# SW6106_A_B_C_Lighting_LED.net
KiCad netlist of a schematic drawn in Altium Designer
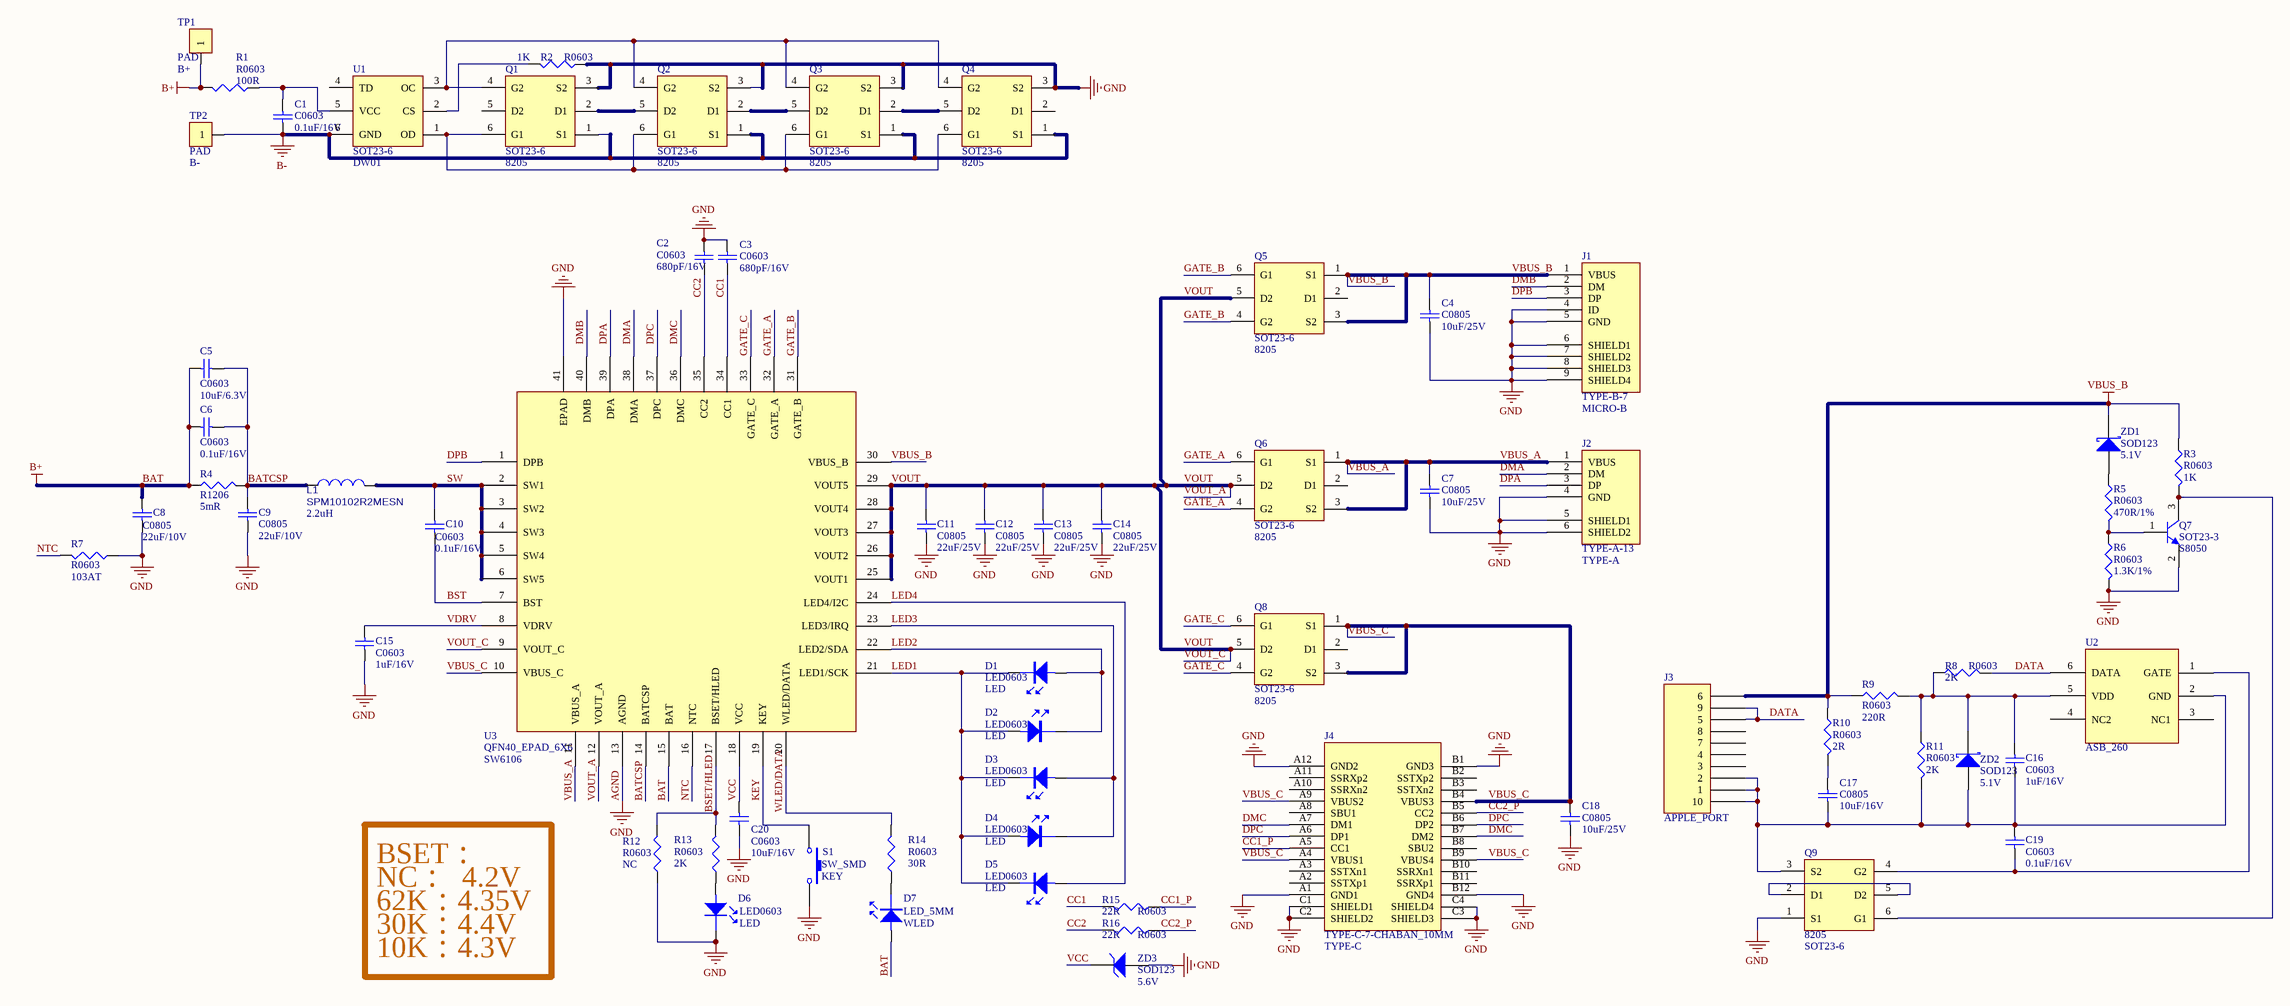
[diagram p0: SW6106+A+B+C+Lighting+LED.SchDoc]

(export (version "E")
  (design (tool "Eeschema 10.0.6"))
  (components
    (comp (ref "C1")
      (value "C0603")
      (footprint "C0603")
      (description "Capacitor")
      (fields (field (name "ALTIUM_VALUE") "0.1uF/16V") (field (name "PUBLISHER") "Altium Limited"))
      (libsource (lib "*") (part "Cap"))
    )
    (comp (ref "C2")
      (value "C0603")
      (footprint "C0603")
      (description "Capacitor")
      (fields (field (name "ALTIUM_VALUE") "680pF/16V") (field (name "PUBLISHER") "Altium Limited"))
      (libsource (lib "*") (part "CAP0603"))
    )
    (comp (ref "C3")
      (value "C0603")
      (footprint "C0603")
      (description "Capacitor")
      (fields (field (name "ALTIUM_VALUE") "680pF/16V") (field (name "PUBLISHER") "Altium Limited"))
      (libsource (lib "*") (part "CAP0603"))
    )
    (comp (ref "C4")
      (value "C0805")
      (footprint "C0805")
      (description "Capacitor")
      (fields (field (name "ALTIUM_VALUE") "10uF/25V") (field (name "PUBLISHER") "Altium Limited"))
      (libsource (lib "*") (part "CAP0603"))
    )
    (comp (ref "C5")
      (value "C0603")
      (footprint "C0603")
      (description "Capacitor")
      (fields (field (name "ALTIUM_VALUE") "10uF/6.3V") (field (name "PUBLISHER") "Altium Limited"))
      (libsource (lib "*") (part "CAP0603"))
    )
    (comp (ref "C6")
      (value "C0603")
      (footprint "C0603")
      (description "Capacitor")
      (fields (field (name "ALTIUM_VALUE") "0.1uF/16V") (field (name "PUBLISHER") "Altium Limited"))
      (libsource (lib "*") (part "CAP0603"))
    )
    (comp (ref "C7")
      (value "C0805")
      (footprint "C0805")
      (description "Capacitor")
      (fields (field (name "ALTIUM_VALUE") "10uF/25V") (field (name "PUBLISHER") "Altium Limited"))
      (libsource (lib "*") (part "CAP0603"))
    )
    (comp (ref "C8")
      (value "C0805")
      (footprint "C0805")
      (description "Capacitor")
      (fields (field (name "ALTIUM_VALUE") "22uF/10V") (field (name "PUBLISHER") "Altium Limited"))
      (libsource (lib "*") (part "CAP0805"))
    )
    (comp (ref "C9")
      (value "C0805")
      (footprint "C0805")
      (description "Capacitor")
      (fields (field (name "ALTIUM_VALUE") "22uF/10V") (field (name "PUBLISHER") "Altium Limited"))
      (libsource (lib "*") (part "CAP0805"))
    )
    (comp (ref "C10")
      (value "C0603")
      (footprint "C0603")
      (description "Capacitor")
      (fields (field (name "ALTIUM_VALUE") "0.1uF/16V") (field (name "PUBLISHER") "Altium Limited"))
      (libsource (lib "*") (part "CAP0603"))
    )
    (comp (ref "C11")
      (value "C0805")
      (footprint "C0805")
      (description "Capacitor")
      (fields (field (name "ALTIUM_VALUE") "22uF/25V") (field (name "PUBLISHER") "Altium Limited"))
      (libsource (lib "*") (part "CAP0805"))
    )
    (comp (ref "C12")
      (value "C0805")
      (footprint "C0805")
      (description "Capacitor")
      (fields (field (name "ALTIUM_VALUE") "22uF/25V") (field (name "PUBLISHER") "Altium Limited"))
      (libsource (lib "*") (part "CAP0805"))
    )
    (comp (ref "C13")
      (value "C0805")
      (footprint "C0805")
      (description "Capacitor")
      (fields (field (name "ALTIUM_VALUE") "22uF/25V") (field (name "PUBLISHER") "Altium Limited"))
      (libsource (lib "*") (part "CAP0805"))
    )
    (comp (ref "C14")
      (value "C0805")
      (footprint "C0805")
      (description "Capacitor")
      (fields (field (name "ALTIUM_VALUE") "22uF/25V") (field (name "PUBLISHER") "Altium Limited"))
      (libsource (lib "*") (part "CAP0805"))
    )
    (comp (ref "C15")
      (value "C0603")
      (footprint "C0603")
      (description "Capacitor")
      (fields (field (name "ALTIUM_VALUE") "1uF/16V") (field (name "PUBLISHER") "Altium Limited"))
      (libsource (lib "*") (part "CAP0603"))
    )
    (comp (ref "C16")
      (value "C0603")
      (footprint "C0603")
      (description "Capacitor")
      (fields (field (name "ALTIUM_VALUE") "1uF/16V") (field (name "PUBLISHER") "Altium Limited"))
      (libsource (lib "*") (part "CAP0805"))
    )
    (comp (ref "C17")
      (value "C0805")
      (footprint "C0805")
      (description "Capacitor")
      (fields (field (name "ALTIUM_VALUE") "10uF/16V") (field (name "PUBLISHER") "Altium Limited"))
      (libsource (lib "*") (part "CAP0805"))
    )
    (comp (ref "C18")
      (value "C0805")
      (footprint "C0805")
      (description "Capacitor")
      (fields (field (name "ALTIUM_VALUE") "10uF/25V") (field (name "PUBLISHER") "Altium Limited"))
      (libsource (lib "*") (part "CAP0603"))
    )
    (comp (ref "C19")
      (value "C0603")
      (footprint "C0603")
      (description "Capacitor")
      (fields (field (name "ALTIUM_VALUE") "0.1uF/16V") (field (name "PUBLISHER") "Altium Limited"))
      (libsource (lib "*") (part "CAP0805"))
    )
    (comp (ref "C20")
      (value "C0603")
      (footprint "C0603")
      (description "Capacitor")
      (fields (field (name "ALTIUM_VALUE") "10uF/16V") (field (name "PUBLISHER") "Altium Limited"))
      (libsource (lib "*") (part "CAP0603"))
    )
    (comp (ref "D1") (value "LED") (footprint "LED0603") (libsource (lib "*") (part "LED")))
    (comp (ref "D2") (value "LED") (footprint "LED0603") (libsource (lib "*") (part "LED")))
    (comp (ref "D3") (value "LED") (footprint "LED0603") (libsource (lib "*") (part "LED")))
    (comp (ref "D4") (value "LED") (footprint "LED0603") (libsource (lib "*") (part "LED")))
    (comp (ref "D5") (value "LED") (footprint "LED0603") (libsource (lib "*") (part "LED")))
    (comp (ref "D6") (value "LED") (footprint "LED0603") (libsource (lib "*") (part "LED")))
    (comp (ref "D7")
      (value "WLED")
      (footprint "LED_5MM")
      (fields (field (name "FOOTPRINF") "LED_5MM") (field (name "Comment") "LED_5MM"))
      (libsource (lib "*") (part "LED"))
    )
    (comp (ref "J1")
      (value "MICRO-B")
      (footprint "TYPE-B-7")
      (fields (field (name "FOOTPRINTF") "TYPE-B-7") (field (name "Comment") "USB_MICRO_B"))
      (libsource (lib "*") (part "USB_MICRO_B"))
    )
    (comp (ref "J2")
      (value "TYPE-A")
      (footprint "TYPE-A-13")
      (fields (field (name "FOOTPRINF") "TYPE-A-13") (field (name "Comment") "TYPE-A-1"))
      (libsource (lib "*") (part "TYPE-A-1"))
    )
    (comp (ref "J3") (value "APPLE_PORT") (libsource (lib "TEST") (part "APPLE_PORT")))
    (comp (ref "J4")
      (value "TYPE-C")
      (footprint "TYPE-C-7-CHABAN_10MM")
      (libsource (lib "*") (part "TYPE-C"))
    )
    (comp (ref "L1")
      (value "SPM10102R2MESN")
      (footprint "INDUCTOR_SPM1010")
      (fields (field (name "ALTIUM_VALUE") "2.2uH"))
      (libsource (lib "*") (part "INDUCTOR"))
    )
    (comp (ref "Q1")
      (value "8205")
      (footprint "SOT23-6")
      (fields (field (name "FOOTPRINF") "SOT23-6"))
      (libsource (lib "") (part "8205B_1"))
    )
    (comp (ref "Q2")
      (value "8205")
      (footprint "SOT23-6")
      (fields (field (name "FOOTPRINF") "SOT23-6"))
      (libsource (lib "") (part "8205B_1"))
    )
    (comp (ref "Q3")
      (value "8205")
      (footprint "SOT23-6")
      (fields (field (name "FOOTPRINF") "SOT23-6"))
      (libsource (lib "") (part "8205B_1"))
    )
    (comp (ref "Q4")
      (value "8205")
      (footprint "SOT23-6")
      (fields (field (name "FOOTPRINF") "SOT23-6"))
      (libsource (lib "") (part "8205B_1"))
    )
    (comp (ref "Q5")
      (value "8205")
      (footprint "SOT23-6")
      (fields (field (name "FOOTPRINF") "SOT23-6"))
      (libsource (lib "*") (part "8205B"))
    )
    (comp (ref "Q6")
      (value "8205")
      (footprint "SOT23-6")
      (fields (field (name "FOOTPRINF") "SOT23-6"))
      (libsource (lib "*") (part "8205B"))
    )
    (comp (ref "Q7")
      (value "S8050")
      (footprint "SOT23-3")
      (description "NPN General Purpose Amplifier")
      (fields (field (name "PUBLISHER") "Altium Limited"))
      (libsource (lib "Miscellaneous Devices") (part "2N3904"))
    )
    (comp (ref "Q8")
      (value "8205")
      (footprint "SOT23-6")
      (fields (field (name "FOOTPRINF") "SOT23-6"))
      (libsource (lib "*") (part "8205B"))
    )
    (comp (ref "Q9")
      (value "8205")
      (footprint "SOT23-6")
      (fields (field (name "FOOTPRINF") "SOT23-6"))
      (libsource (lib "") (part "8205B_2"))
    )
    (comp (ref "R1")
      (value "R0603")
      (footprint "R0603")
      (description "Resistor")
      (fields (field (name "ALTIUM_VALUE") "100R") (field (name "PUBLISHER") "Altium Limited"))
      (libsource (lib "*") (part "Res3"))
    )
    (comp (ref "R2")
      (value "R0603")
      (footprint "R0603")
      (description "Resistor")
      (fields (field (name "ALTIUM_VALUE") "1K") (field (name "PUBLISHER") "Altium Limited"))
      (libsource (lib "*") (part "Res3"))
    )
    (comp (ref "R3")
      (value "R0603")
      (footprint "R0603")
      (description "Resistor")
      (fields (field (name "ALTIUM_VALUE") "1K") (field (name "PUBLISHER") "Altium Limited"))
      (libsource (lib "Miscellaneous Devices") (part "Res3"))
    )
    (comp (ref "R4")
      (value "R1206")
      (footprint "R1206")
      (description "Resistor")
      (fields (field (name "ALTIUM_VALUE") "5mR") (field (name "PUBLISHER") "Altium Limited"))
      (libsource (lib "*") (part "RES"))
    )
    (comp (ref "R5")
      (value "R0603")
      (footprint "R0603")
      (description "Resistor")
      (fields (field (name "ALTIUM_VALUE") "470R/1%") (field (name "PUBLISHER") "Altium Limited"))
      (libsource (lib "Miscellaneous Devices") (part "Res3"))
    )
    (comp (ref "R6")
      (value "R0603")
      (footprint "R0603")
      (description "Resistor")
      (fields (field (name "ALTIUM_VALUE") "1.3K/1%") (field (name "PUBLISHER") "Altium Limited"))
      (libsource (lib "Miscellaneous Devices") (part "Res3"))
    )
    (comp (ref "R7")
      (value "R0603")
      (footprint "R0603")
      (description "Resistor")
      (fields (field (name "ALTIUM_VALUE") "103AT") (field (name "PUBLISHER") "Altium Limited"))
      (libsource (lib "*") (part "RES"))
    )
    (comp (ref "R8")
      (value "R0603")
      (footprint "R0603")
      (description "Resistor")
      (fields (field (name "ALTIUM_VALUE") "2K") (field (name "PUBLISHER") "Altium Limited"))
      (libsource (lib "Miscellaneous Devices") (part "Res3"))
    )
    (comp (ref "R9")
      (value "R0603")
      (footprint "R0603")
      (description "Resistor")
      (fields (field (name "ALTIUM_VALUE") "220R") (field (name "PUBLISHER") "Altium Limited"))
      (libsource (lib "Miscellaneous Devices") (part "Res3"))
    )
    (comp (ref "R10")
      (value "R0603")
      (footprint "R0603")
      (description "Resistor")
      (fields (field (name "ALTIUM_VALUE") "2R") (field (name "PUBLISHER") "Altium Limited"))
      (libsource (lib "Miscellaneous Devices") (part "Res3"))
    )
    (comp (ref "R11")
      (value "R0603")
      (footprint "R0603")
      (description "Resistor")
      (fields (field (name "ALTIUM_VALUE") "2K") (field (name "PUBLISHER") "Altium Limited"))
      (libsource (lib "Miscellaneous Devices") (part "Res3"))
    )
    (comp (ref "R12")
      (value "R0603")
      (footprint "R0603")
      (description "Resistor")
      (fields (field (name "ALTIUM_VALUE") "NC") (field (name "PUBLISHER") "Altium Limited"))
      (libsource (lib "*") (part "RES"))
    )
    (comp (ref "R13")
      (value "R0603")
      (footprint "R0603")
      (description "Resistor")
      (fields (field (name "ALTIUM_VALUE") "2K") (field (name "PUBLISHER") "Altium Limited"))
      (libsource (lib "*") (part "RES"))
    )
    (comp (ref "R14")
      (value "R0603")
      (footprint "R0603")
      (description "Resistor")
      (fields (field (name "ALTIUM_VALUE") "30R") (field (name "PUBLISHER") "Altium Limited"))
      (libsource (lib "*") (part "RES"))
    )
    (comp (ref "R15")
      (value "R0603")
      (footprint "R0603")
      (description "Resistor")
      (fields (field (name "ALTIUM_VALUE") "22R") (field (name "PUBLISHER") "Altium Limited"))
      (libsource (lib "*") (part "RES"))
    )
    (comp (ref "R16")
      (value "R0603")
      (footprint "R0603")
      (description "Resistor")
      (fields (field (name "ALTIUM_VALUE") "22R") (field (name "PUBLISHER") "Altium Limited"))
      (libsource (lib "*") (part "RES"))
    )
    (comp (ref "S1")
      (value "KEY")
      (footprint "SW_SMD")
      (fields (field (name "FOOTPRINF") "SW_SMD"))
      (libsource (lib "*") (part "SW K"))
    )
    (comp (ref "TP1") (value "B+") (footprint "PAD") (libsource (lib "") (part "Test Point_1")))
    (comp (ref "TP2") (value "B-") (footprint "PAD") (libsource (lib "*") (part "Test Point")))
    (comp (ref "U1")
      (value "DW01")
      (footprint "SOT23-6")
      (fields (field (name "FOOTPRINF") "SOT23-6"))
      (libsource (lib "*") (part "DW01"))
    )
    (comp (ref "U2") (value "ASB_260") (footprint "SOT-23-") (libsource (lib "TEST") (part "ASB_260")))
    (comp (ref "U3")
      (value "SW6106")
      (footprint "QFN40_EPAD_6X6")
      (libsource (lib "TEST") (part "SW6106_AFC"))
    )
    (comp (ref "ZD1")
      (value "5.1V")
      (footprint "SOD123")
      (description "Schottky Rectifier")
      (fields (field (name "Comment") "Diode 11DQ03") (field (name "PUBLISHER") "Altium Limited"))
      (libsource (lib "Miscellaneous Devices") (part "Diode 11DQ03"))
    )
    (comp (ref "ZD2")
      (value "5.1V")
      (footprint "SOD123")
      (description "Schottky Rectifier")
      (fields (field (name "Comment") "Diode 11DQ03") (field (name "PUBLISHER") "Altium Limited"))
      (libsource (lib "Miscellaneous Devices") (part "Diode 11DQ03"))
    )
    (comp (ref "ZD3")
      (value "SOD123")
      (footprint "SOD-123")
      (description "Zener Diode")
      (fields (field (name "ALTIUM_UNNAMED_1") "5.6V"))
      (libsource (lib "Miscellaneous Devices") (part "D Zener"))
    )
  )
  (nets
    (net (code "1") (name "/BATCSP") (class "Default")
      (node (ref "C5") (pin "2") (pinfunction "2_2") (pintype "passive"))
      (node (ref "C6") (pin "2") (pinfunction "2_2") (pintype "passive"))
      (node (ref "C9") (pin "2") (pinfunction "2_2") (pintype "passive"))
      (node (ref "L1") (pin "1") (pinfunction "1_1") (pintype "passive"))
      (node (ref "R4") (pin "2") (pinfunction "2_2") (pintype "passive"))
      (node (ref "U3") (pin "14") (pinfunction "BATCSP_14") (pintype "passive"))
    )
    (net (code "2") (name "/BSET{slash}HLED") (class "Default")
      (node (ref "R12") (pin "2") (pinfunction "2_2") (pintype "passive"))
      (node (ref "R13") (pin "2") (pinfunction "2_2") (pintype "passive"))
      (node (ref "U3") (pin "17") (pinfunction "BSET/HLED_17") (pintype "passive"))
    )
    (net (code "3") (name "/BST") (class "Default")
      (node (ref "C10") (pin "1") (pinfunction "1_1") (pintype "passive"))
      (node (ref "U3") (pin "7") (pinfunction "BST_7") (pintype "passive"))
    )
    (net (code "4") (name "/CC1") (class "Default")
      (node (ref "C3") (pin "1") (pinfunction "1_1") (pintype "passive"))
      (node (ref "R15") (pin "2") (pinfunction "2_2") (pintype "passive"))
      (node (ref "U3") (pin "34") (pinfunction "CC1_34") (pintype "passive"))
    )
    (net (code "5") (name "/CC1_P") (class "Default")
      (node (ref "J4") (pin "A5") (pinfunction "CC1_A5") (pintype "passive"))
      (node (ref "R15") (pin "1") (pinfunction "1_1") (pintype "passive"))
    )
    (net (code "6") (name "/CC2") (class "Default")
      (node (ref "C2") (pin "1") (pinfunction "1_1") (pintype "passive"))
      (node (ref "R16") (pin "2") (pinfunction "2_2") (pintype "passive"))
      (node (ref "U3") (pin "35") (pinfunction "CC2_35") (pintype "passive"))
    )
    (net (code "7") (name "/CC2_P") (class "Default")
      (node (ref "J4") (pin "B5") (pinfunction "CC2_B5") (pintype "passive"))
      (node (ref "R16") (pin "1") (pinfunction "1_1") (pintype "passive"))
    )
    (net (code "8") (name "/DATA") (class "Default")
      (node (ref "J3") (pin "5") (pinfunction "5_5") (pintype "passive"))
      (node (ref "J3") (pin "9") (pinfunction "9_9") (pintype "passive"))
      (node (ref "R8") (pin "2") (pinfunction "2_2") (pintype "passive"))
      (node (ref "U2") (pin "6") (pinfunction "DATA_6") (pintype "passive"))
    )
    (net (code "9") (name "/DMA") (class "Default")
      (node (ref "J2") (pin "2") (pinfunction "DM_2") (pintype "passive"))
      (node (ref "U3") (pin "38") (pinfunction "DMA_38") (pintype "passive"))
    )
    (net (code "10") (name "/DMB") (class "Default")
      (node (ref "J1") (pin "2") (pinfunction "DM_2") (pintype "passive"))
      (node (ref "U3") (pin "40") (pinfunction "DMB_40") (pintype "passive"))
    )
    (net (code "11") (name "/DMC") (class "Default")
      (node (ref "J4") (pin "A7") (pinfunction "DM1_A7") (pintype "passive"))
      (node (ref "J4") (pin "B7") (pinfunction "DM2_B7") (pintype "passive"))
      (node (ref "U3") (pin "36") (pinfunction "DMC_36") (pintype "passive"))
    )
    (net (code "12") (name "/DPA") (class "Default")
      (node (ref "J2") (pin "3") (pinfunction "DP_3") (pintype "passive"))
      (node (ref "U3") (pin "39") (pinfunction "DPA_39") (pintype "passive"))
    )
    (net (code "13") (name "/DPB") (class "Default")
      (node (ref "J1") (pin "3") (pinfunction "DP_3") (pintype "passive"))
      (node (ref "U3") (pin "1") (pinfunction "DPB_1") (pintype "passive"))
    )
    (net (code "14") (name "/DPC") (class "Default")
      (node (ref "J4") (pin "A6") (pinfunction "DP1_A6") (pintype "passive"))
      (node (ref "J4") (pin "B6") (pinfunction "DP2_B6") (pintype "passive"))
      (node (ref "U3") (pin "37") (pinfunction "DPC_37") (pintype "passive"))
    )
    (net (code "15") (name "/GATE_A") (class "Default")
      (node (ref "Q6") (pin "4") (pinfunction "G2_4") (pintype "passive"))
      (node (ref "Q6") (pin "6") (pinfunction "G1_6") (pintype "passive"))
      (node (ref "U3") (pin "32") (pinfunction "GATE_A_32") (pintype "passive"))
    )
    (net (code "16") (name "/GATE_B") (class "Default")
      (node (ref "Q5") (pin "4") (pinfunction "G2_4") (pintype "passive"))
      (node (ref "Q5") (pin "6") (pinfunction "G1_6") (pintype "passive"))
      (node (ref "U3") (pin "31") (pinfunction "GATE_B_31") (pintype "passive"))
    )
    (net (code "17") (name "/GATE_C") (class "Default")
      (node (ref "Q8") (pin "4") (pinfunction "G2_4") (pintype "passive"))
      (node (ref "Q8") (pin "6") (pinfunction "G1_6") (pintype "passive"))
      (node (ref "U3") (pin "33") (pinfunction "GATE_C_33") (pintype "passive"))
    )
    (net (code "18") (name "/KEY") (class "Default")
      (node (ref "S1") (pin "1") (pinfunction "1_1") (pintype "passive"))
      (node (ref "U3") (pin "19") (pinfunction "KEY_19") (pintype "passive"))
    )
    (net (code "19") (name "/LED1") (class "Default")
      (node (ref "D1") (pin "2") (pinfunction "K_2") (pintype "passive"))
      (node (ref "D2") (pin "1") (pinfunction "A_1") (pintype "passive"))
      (node (ref "D3") (pin "2") (pinfunction "K_2") (pintype "passive"))
      (node (ref "D4") (pin "1") (pinfunction "A_1") (pintype "passive"))
      (node (ref "D5") (pin "2") (pinfunction "K_2") (pintype "passive"))
      (node (ref "U3") (pin "21") (pinfunction "LED1/SCK_21") (pintype "passive"))
    )
    (net (code "20") (name "/LED2") (class "Default")
      (node (ref "D1") (pin "1") (pinfunction "A_1") (pintype "passive"))
      (node (ref "D2") (pin "2") (pinfunction "K_2") (pintype "passive"))
      (node (ref "U3") (pin "22") (pinfunction "LED2/SDA_22") (pintype "passive"))
    )
    (net (code "21") (name "/LED3") (class "Default")
      (node (ref "D3") (pin "1") (pinfunction "A_1") (pintype "passive"))
      (node (ref "D4") (pin "2") (pinfunction "K_2") (pintype "passive"))
      (node (ref "U3") (pin "23") (pinfunction "LED3/IRQ_23") (pintype "passive"))
    )
    (net (code "22") (name "/LED4") (class "Default")
      (node (ref "D5") (pin "1") (pinfunction "A_1") (pintype "passive"))
      (node (ref "U3") (pin "24") (pinfunction "LED4/I2C_24") (pintype "passive"))
    )
    (net (code "23") (name "/NTC") (class "Default")
      (node (ref "R7") (pin "2") (pinfunction "2_2") (pintype "passive"))
      (node (ref "U3") (pin "16") (pinfunction "NTC_16") (pintype "passive"))
    )
    (net (code "24") (name "/SW") (class "Default")
      (node (ref "C10") (pin "2") (pinfunction "2_2") (pintype "passive"))
      (node (ref "L1") (pin "2") (pinfunction "2_2") (pintype "passive"))
      (node (ref "U3") (pin "2") (pinfunction "SW1_2") (pintype "passive"))
      (node (ref "U3") (pin "3") (pinfunction "SW2_3") (pintype "passive"))
      (node (ref "U3") (pin "4") (pinfunction "SW3_4") (pintype "passive"))
      (node (ref "U3") (pin "5") (pinfunction "SW4_5") (pintype "passive"))
      (node (ref "U3") (pin "6") (pinfunction "SW5_6") (pintype "passive"))
    )
    (net (code "25") (name "/VBUS_A") (class "Default")
      (node (ref "C7") (pin "2") (pinfunction "2_2") (pintype "passive"))
      (node (ref "J2") (pin "1") (pinfunction "VBUS_1") (pintype "passive"))
      (node (ref "Q6") (pin "1") (pinfunction "S1_1") (pintype "passive"))
      (node (ref "Q6") (pin "3") (pinfunction "S2_3") (pintype "passive"))
      (node (ref "U3") (pin "11") (pinfunction "VBUS_A_11") (pintype "passive"))
    )
    (net (code "26") (name "/VBUS_C") (class "Default")
      (node (ref "C18") (pin "2") (pinfunction "2_2") (pintype "passive"))
      (node (ref "J4") (pin "A4") (pinfunction "VBUS1_A4") (pintype "passive"))
      (node (ref "J4") (pin "A9") (pinfunction "VBUS2_A9") (pintype "passive"))
      (node (ref "J4") (pin "B4") (pinfunction "VBUS3_B4") (pintype "passive"))
      (node (ref "J4") (pin "B9") (pinfunction "VBUS4_B9") (pintype "passive"))
      (node (ref "Q8") (pin "1") (pinfunction "S1_1") (pintype "passive"))
      (node (ref "Q8") (pin "3") (pinfunction "S2_3") (pintype "passive"))
      (node (ref "U3") (pin "10") (pinfunction "VBUS_C_10") (pintype "passive"))
    )
    (net (code "27") (name "/VCC") (class "Default")
      (node (ref "C20") (pin "2") (pinfunction "2_2") (pintype "passive"))
      (node (ref "U3") (pin "18") (pinfunction "VCC_18") (pintype "passive"))
      (node (ref "ZD3") (pin "2") (pinfunction "K_2") (pintype "passive"))
    )
    (net (code "28") (name "/VDRV") (class "Default")
      (node (ref "C15") (pin "2") (pinfunction "2_2") (pintype "passive"))
      (node (ref "U3") (pin "8") (pinfunction "VDRV_8") (pintype "passive"))
    )
    (net (code "29") (name "/VOUT") (class "Default")
      (node (ref "C11") (pin "2") (pinfunction "2_2") (pintype "passive"))
      (node (ref "C12") (pin "2") (pinfunction "2_2") (pintype "passive"))
      (node (ref "C13") (pin "2") (pinfunction "2_2") (pintype "passive"))
      (node (ref "C14") (pin "2") (pinfunction "2_2") (pintype "passive"))
      (node (ref "Q5") (pin "5") (pinfunction "D2_5") (pintype "passive"))
      (node (ref "Q6") (pin "5") (pinfunction "D2_5") (pintype "passive"))
      (node (ref "Q8") (pin "5") (pinfunction "D2_5") (pintype "passive"))
      (node (ref "U3") (pin "12") (pinfunction "VOUT_A_12") (pintype "passive"))
      (node (ref "U3") (pin "25") (pinfunction "VOUT1_25") (pintype "passive"))
      (node (ref "U3") (pin "26") (pinfunction "VOUT2_26") (pintype "passive"))
      (node (ref "U3") (pin "27") (pinfunction "VOUT3_27") (pintype "passive"))
      (node (ref "U3") (pin "28") (pinfunction "VOUT4_28") (pintype "passive"))
      (node (ref "U3") (pin "29") (pinfunction "VOUT5_29") (pintype "passive"))
      (node (ref "U3") (pin "9") (pinfunction "VOUT_C_9") (pintype "passive"))
    )
    (net (code "30") (name "/WLED{slash}DATA") (class "Default")
      (node (ref "R14") (pin "2") (pinfunction "2_2") (pintype "passive"))
      (node (ref "U3") (pin "20") (pinfunction "WLED/DATA_20") (pintype "passive"))
    )
    (net (code "31") (name "B+") (class "Default")
      (node (ref "C5") (pin "1") (pinfunction "1_1") (pintype "passive"))
      (node (ref "C6") (pin "1") (pinfunction "1_1") (pintype "passive"))
      (node (ref "C8") (pin "2") (pinfunction "2_2") (pintype "passive"))
      (node (ref "D7") (pin "1") (pinfunction "A_1") (pintype "passive"))
      (node (ref "R1") (pin "2") (pinfunction "2_2") (pintype "passive"))
      (node (ref "R4") (pin "1") (pinfunction "1_1") (pintype "passive"))
      (node (ref "TP1") (pin "1") (pinfunction "1_1") (pintype "passive"))
      (node (ref "U3") (pin "15") (pinfunction "BAT_15") (pintype "passive"))
    )
    (net (code "32") (name "B-") (class "Default")
      (node (ref "C1") (pin "1") (pinfunction "1_1") (pintype "passive"))
      (node (ref "Q1") (pin "1") (pinfunction "S1_1") (pintype "passive"))
      (node (ref "Q2") (pin "1") (pinfunction "S1_1") (pintype "passive"))
      (node (ref "Q3") (pin "1") (pinfunction "S1_1") (pintype "passive"))
      (node (ref "Q4") (pin "1") (pinfunction "S1_1") (pintype "passive"))
      (node (ref "TP2") (pin "1") (pinfunction "1_1") (pintype "passive"))
      (node (ref "U1") (pin "6") (pinfunction "GND_6") (pintype "passive"))
    )
    (net (code "33") (name "GND") (class "Default")
      (node (ref "C11") (pin "1") (pinfunction "1_1") (pintype "passive"))
      (node (ref "C12") (pin "1") (pinfunction "1_1") (pintype "passive"))
      (node (ref "C13") (pin "1") (pinfunction "1_1") (pintype "passive"))
      (node (ref "C14") (pin "1") (pinfunction "1_1") (pintype "passive"))
      (node (ref "C15") (pin "1") (pinfunction "1_1") (pintype "passive"))
      (node (ref "C18") (pin "1") (pinfunction "1_1") (pintype "passive"))
      (node (ref "C2") (pin "2") (pinfunction "2_2") (pintype "passive"))
      (node (ref "C20") (pin "1") (pinfunction "1_1") (pintype "passive"))
      (node (ref "C3") (pin "2") (pinfunction "2_2") (pintype "passive"))
      (node (ref "C4") (pin "1") (pinfunction "1_1") (pintype "passive"))
      (node (ref "C7") (pin "1") (pinfunction "1_1") (pintype "passive"))
      (node (ref "C8") (pin "1") (pinfunction "1_1") (pintype "passive"))
      (node (ref "C9") (pin "1") (pinfunction "1_1") (pintype "passive"))
      (node (ref "D6") (pin "2") (pinfunction "K_2") (pintype "passive"))
      (node (ref "J1") (pin "4") (pinfunction "ID_4") (pintype "passive"))
      (node (ref "J1") (pin "5") (pinfunction "GND_5") (pintype "passive"))
      (node (ref "J1") (pin "6") (pinfunction "SHIELD1_6") (pintype "passive"))
      (node (ref "J1") (pin "7") (pinfunction "SHIELD2_7") (pintype "passive"))
      (node (ref "J1") (pin "8") (pinfunction "SHIELD3_8") (pintype "passive"))
      (node (ref "J1") (pin "9") (pinfunction "SHIELD4_9") (pintype "passive"))
      (node (ref "J2") (pin "4") (pinfunction "GND_4") (pintype "passive"))
      (node (ref "J2") (pin "5") (pinfunction "SHIELD1_5") (pintype "passive"))
      (node (ref "J2") (pin "6") (pinfunction "SHIELD2_6") (pintype "passive"))
      (node (ref "J4") (pin "A1") (pinfunction "GND1_A1") (pintype "passive"))
      (node (ref "J4") (pin "A12") (pinfunction "GND2_A12") (pintype "passive"))
      (node (ref "J4") (pin "B1") (pinfunction "GND3_B1") (pintype "passive"))
      (node (ref "J4") (pin "B12") (pinfunction "GND4_B12") (pintype "passive"))
      (node (ref "J4") (pin "C1") (pinfunction "SHIELD1_C1") (pintype "passive"))
      (node (ref "J4") (pin "C2") (pinfunction "SHIELD2_C2") (pintype "passive"))
      (node (ref "J4") (pin "C3") (pinfunction "SHIELD3_C3") (pintype "passive"))
      (node (ref "J4") (pin "C4") (pinfunction "SHIELD4_C4") (pintype "passive"))
      (node (ref "Q1") (pin "3") (pinfunction "S2_3") (pintype "passive"))
      (node (ref "Q2") (pin "3") (pinfunction "S2_3") (pintype "passive"))
      (node (ref "Q3") (pin "3") (pinfunction "S2_3") (pintype "passive"))
      (node (ref "Q4") (pin "3") (pinfunction "S2_3") (pintype "passive"))
      (node (ref "Q7") (pin "2") (pinfunction "E_2") (pintype "passive"))
      (node (ref "Q9") (pin "1") (pinfunction "S1_1") (pintype "passive"))
      (node (ref "R12") (pin "1") (pinfunction "1_1") (pintype "passive"))
      (node (ref "R2") (pin "1") (pinfunction "1_1") (pintype "passive"))
      (node (ref "R6") (pin "2") (pinfunction "2_2") (pintype "passive"))
      (node (ref "R7") (pin "1") (pinfunction "1_1") (pintype "passive"))
      (node (ref "S1") (pin "2") (pinfunction "2_2") (pintype "passive"))
      (node (ref "U3") (pin "13") (pinfunction "AGND_13") (pintype "passive"))
      (node (ref "U3") (pin "41") (pinfunction "EPAD_41") (pintype "passive"))
      (node (ref "ZD3") (pin "1") (pinfunction "A_1") (pintype "passive"))
    )
    (net (code "34") (name "Net-(C17-Pad2)") (class "Default")
      (node (ref "C17") (pin "2") (pinfunction "2_2") (pintype "passive"))
      (node (ref "R10") (pin "2") (pinfunction "2_2") (pintype "passive"))
    )
    (net (code "35") (name "Net-(D6-A)") (class "Default")
      (node (ref "D6") (pin "1") (pinfunction "A_1") (pintype "passive"))
      (node (ref "R13") (pin "1") (pinfunction "1_1") (pintype "passive"))
    )
    (net (code "36") (name "Net-(D7-K)") (class "Default")
      (node (ref "D7") (pin "2") (pinfunction "K_2") (pintype "passive"))
      (node (ref "R14") (pin "1") (pinfunction "1_1") (pintype "passive"))
    )
    (net (code "37") (name "Net-(Q1-D1)") (class "Default")
      (node (ref "Q1") (pin "2") (pinfunction "D1_2") (pintype "passive"))
      (node (ref "Q2") (pin "5") (pinfunction "D2_5") (pintype "passive"))
    )
    (net (code "38") (name "Net-(Q1-G1)") (class "Default")
      (node (ref "Q1") (pin "6") (pinfunction "G1_6") (pintype "passive"))
      (node (ref "Q2") (pin "6") (pinfunction "G1_6") (pintype "passive"))
      (node (ref "Q3") (pin "6") (pinfunction "G1_6") (pintype "passive"))
      (node (ref "Q4") (pin "6") (pinfunction "G1_6") (pintype "passive"))
      (node (ref "U1") (pin "1") (pinfunction "OD_1") (pintype "passive"))
    )
    (net (code "39") (name "Net-(Q1-G2)") (class "Default")
      (node (ref "Q1") (pin "4") (pinfunction "G2_4") (pintype "passive"))
      (node (ref "Q2") (pin "4") (pinfunction "G2_4") (pintype "passive"))
      (node (ref "Q3") (pin "4") (pinfunction "G2_4") (pintype "passive"))
      (node (ref "Q4") (pin "4") (pinfunction "G2_4") (pintype "passive"))
      (node (ref "U1") (pin "3") (pinfunction "OC_3") (pintype "passive"))
    )
    (net (code "40") (name "Net-(Q2-D1)") (class "Default")
      (node (ref "Q2") (pin "2") (pinfunction "D1_2") (pintype "passive"))
      (node (ref "Q3") (pin "5") (pinfunction "D2_5") (pintype "passive"))
    )
    (net (code "41") (name "Net-(Q3-D1)") (class "Default")
      (node (ref "Q3") (pin "2") (pinfunction "D1_2") (pintype "passive"))
      (node (ref "Q4") (pin "5") (pinfunction "D2_5") (pintype "passive"))
    )
    (net (code "42") (name "Net-(Q7-B)") (class "Default")
      (node (ref "Q7") (pin "1") (pinfunction "B_1") (pintype "passive"))
      (node (ref "R5") (pin "2") (pinfunction "2_2") (pintype "passive"))
      (node (ref "R6") (pin "1") (pinfunction "1_1") (pintype "passive"))
    )
    (net (code "43") (name "Net-(Q7-C)") (class "Default")
      (node (ref "Q7") (pin "3") (pinfunction "C_3") (pintype "passive"))
      (node (ref "Q9") (pin "6") (pinfunction "G1_6") (pintype "passive"))
      (node (ref "R3") (pin "2") (pinfunction "2_2") (pintype "passive"))
    )
    (net (code "44") (name "Net-(Q9-D1)") (class "Default")
      (node (ref "Q9") (pin "2") (pinfunction "D1_2") (pintype "passive"))
      (node (ref "Q9") (pin "5") (pinfunction "D2_5") (pintype "passive"))
    )
    (net (code "45") (name "Net-(Q9-G2)") (class "Default")
      (node (ref "C19") (pin "1") (pinfunction "1_1") (pintype "passive"))
      (node (ref "Q9") (pin "4") (pinfunction "G2_4") (pintype "passive"))
      (node (ref "U2") (pin "1") (pinfunction "GATE_1") (pintype "passive"))
    )
    (net (code "46") (name "Net-(Q9-S2)") (class "Default")
      (node (ref "C16") (pin "1") (pinfunction "1_1") (pintype "passive"))
      (node (ref "C17") (pin "1") (pinfunction "1_1") (pintype "passive"))
      (node (ref "C19") (pin "2") (pinfunction "2_2") (pintype "passive"))
      (node (ref "J3") (pin "1") (pinfunction "1_1") (pintype "passive"))
      (node (ref "J3") (pin "10") (pinfunction "10_10") (pintype "passive"))
      (node (ref "J3") (pin "2") (pinfunction "2_2") (pintype "passive"))
      (node (ref "Q9") (pin "3") (pinfunction "S2_3") (pintype "passive"))
      (node (ref "R11") (pin "2") (pinfunction "2_2") (pintype "passive"))
      (node (ref "U2") (pin "2") (pinfunction "GND_2") (pintype "passive"))
      (node (ref "ZD2") (pin "1") (pinfunction "A_1") (pintype "passive"))
    )
    (net (code "47") (name "Net-(U1-CS)") (class "Default")
      (node (ref "R2") (pin "2") (pinfunction "2_2") (pintype "passive"))
      (node (ref "U1") (pin "2") (pinfunction "CS_2") (pintype "passive"))
    )
    (net (code "48") (name "Net-(U1-VCC)") (class "Default")
      (node (ref "C1") (pin "2") (pinfunction "2_2") (pintype "passive"))
      (node (ref "R1") (pin "1") (pinfunction "1_1") (pintype "passive"))
      (node (ref "U1") (pin "5") (pinfunction "VCC_5") (pintype "passive"))
    )
    (net (code "49") (name "Net-(U2-VDD)") (class "Default")
      (node (ref "C16") (pin "2") (pinfunction "2_2") (pintype "passive"))
      (node (ref "R11") (pin "1") (pinfunction "1_1") (pintype "passive"))
      (node (ref "R8") (pin "1") (pinfunction "1_1") (pintype "passive"))
      (node (ref "R9") (pin "2") (pinfunction "2_2") (pintype "passive"))
      (node (ref "U2") (pin "5") (pinfunction "VDD_5") (pintype "passive"))
      (node (ref "ZD2") (pin "2") (pinfunction "K_2") (pintype "passive"))
    )
    (net (code "50") (name "Net-(ZD1-A)") (class "Default")
      (node (ref "R5") (pin "1") (pinfunction "1_1") (pintype "passive"))
      (node (ref "ZD1") (pin "1") (pinfunction "A_1") (pintype "passive"))
    )
    (net (code "51") (name "VBUS_B") (class "Default")
      (node (ref "C4") (pin "2") (pinfunction "2_2") (pintype "passive"))
      (node (ref "J1") (pin "1") (pinfunction "VBUS_1") (pintype "passive"))
      (node (ref "J3") (pin "6") (pinfunction "6_6") (pintype "passive"))
      (node (ref "Q5") (pin "1") (pinfunction "S1_1") (pintype "passive"))
      (node (ref "Q5") (pin "3") (pinfunction "S2_3") (pintype "passive"))
      (node (ref "R10") (pin "1") (pinfunction "1_1") (pintype "passive"))
      (node (ref "R3") (pin "1") (pinfunction "1_1") (pintype "passive"))
      (node (ref "R9") (pin "1") (pinfunction "1_1") (pintype "passive"))
      (node (ref "U3") (pin "30") (pinfunction "VBUS_B_30") (pintype "passive"))
      (node (ref "ZD1") (pin "2") (pinfunction "K_2") (pintype "passive"))
    )
    (net (code "52") (name "unconnected-(J3-Pad3)") (class "Default")
      (node (ref "J3") (pin "3") (pinfunction "3_3") (pintype "passive"))
    )
    (net (code "53") (name "unconnected-(J3-Pad4)") (class "Default")
      (node (ref "J3") (pin "4") (pinfunction "4_4") (pintype "passive"))
    )
    (net (code "54") (name "unconnected-(J3-Pad7)") (class "Default")
      (node (ref "J3") (pin "7") (pinfunction "7_7") (pintype "passive"))
    )
    (net (code "55") (name "unconnected-(J3-Pad8)") (class "Default")
      (node (ref "J3") (pin "8") (pinfunction "8_8") (pintype "passive"))
    )
    (net (code "56") (name "unconnected-(J4-SBU1-PadA8)") (class "Default")
      (node (ref "J4") (pin "A8") (pinfunction "SBU1_A8") (pintype "passive"))
    )
    (net (code "57") (name "unconnected-(J4-SBU2-PadB8)") (class "Default")
      (node (ref "J4") (pin "B8") (pinfunction "SBU2_B8") (pintype "passive"))
    )
    (net (code "58") (name "unconnected-(J4-SSRXn1-PadB10)") (class "Default")
      (node (ref "J4") (pin "B10") (pinfunction "SSRXn1_B10") (pintype "passive"))
    )
    (net (code "59") (name "unconnected-(J4-SSRXn2-PadA10)") (class "Default")
      (node (ref "J4") (pin "A10") (pinfunction "SSRXn2_A10") (pintype "passive"))
    )
    (net (code "60") (name "unconnected-(J4-SSRXp1-PadB11)") (class "Default")
      (node (ref "J4") (pin "B11") (pinfunction "SSRXp1_B11") (pintype "passive"))
    )
    (net (code "61") (name "unconnected-(J4-SSRXp2-PadA11)") (class "Default")
      (node (ref "J4") (pin "A11") (pinfunction "SSRXp2_A11") (pintype "passive"))
    )
    (net (code "62") (name "unconnected-(J4-SSTXn1-PadA3)") (class "Default")
      (node (ref "J4") (pin "A3") (pinfunction "SSTXn1_A3") (pintype "passive"))
    )
    (net (code "63") (name "unconnected-(J4-SSTXn2-PadB3)") (class "Default")
      (node (ref "J4") (pin "B3") (pinfunction "SSTXn2_B3") (pintype "passive"))
    )
    (net (code "64") (name "unconnected-(J4-SSTXp1-PadA2)") (class "Default")
      (node (ref "J4") (pin "A2") (pinfunction "SSTXp1_A2") (pintype "passive"))
    )
    (net (code "65") (name "unconnected-(J4-SSTXp2-PadB2)") (class "Default")
      (node (ref "J4") (pin "B2") (pinfunction "SSTXp2_B2") (pintype "passive"))
    )
    (net (code "66") (name "unconnected-(Q1-D2-Pad5)") (class "Default")
      (node (ref "Q1") (pin "5") (pinfunction "D2_5") (pintype "passive"))
    )
    (net (code "67") (name "unconnected-(Q4-D1-Pad2)") (class "Default")
      (node (ref "Q4") (pin "2") (pinfunction "D1_2") (pintype "passive"))
    )
    (net (code "68") (name "unconnected-(Q5-D1-Pad2)") (class "Default")
      (node (ref "Q5") (pin "2") (pinfunction "D1_2") (pintype "passive"))
    )
    (net (code "69") (name "unconnected-(Q6-D1-Pad2)") (class "Default")
      (node (ref "Q6") (pin "2") (pinfunction "D1_2") (pintype "passive"))
    )
    (net (code "70") (name "unconnected-(Q8-D1-Pad2)") (class "Default")
      (node (ref "Q8") (pin "2") (pinfunction "D1_2") (pintype "passive"))
    )
    (net (code "71") (name "unconnected-(U1-TD-Pad4)") (class "Default")
      (node (ref "U1") (pin "4") (pinfunction "TD_4") (pintype "passive"))
    )
    (net (code "72") (name "unconnected-(U2-NC1-Pad3)") (class "Default")
      (node (ref "U2") (pin "3") (pinfunction "NC1_3") (pintype "passive"))
    )
    (net (code "73") (name "unconnected-(U2-NC2-Pad4)") (class "Default")
      (node (ref "U2") (pin "4") (pinfunction "NC2_4") (pintype "passive"))
    )
  )
)
